# LAN8742A.net
KiCad netlist of a schematic drawn in Altium Designer
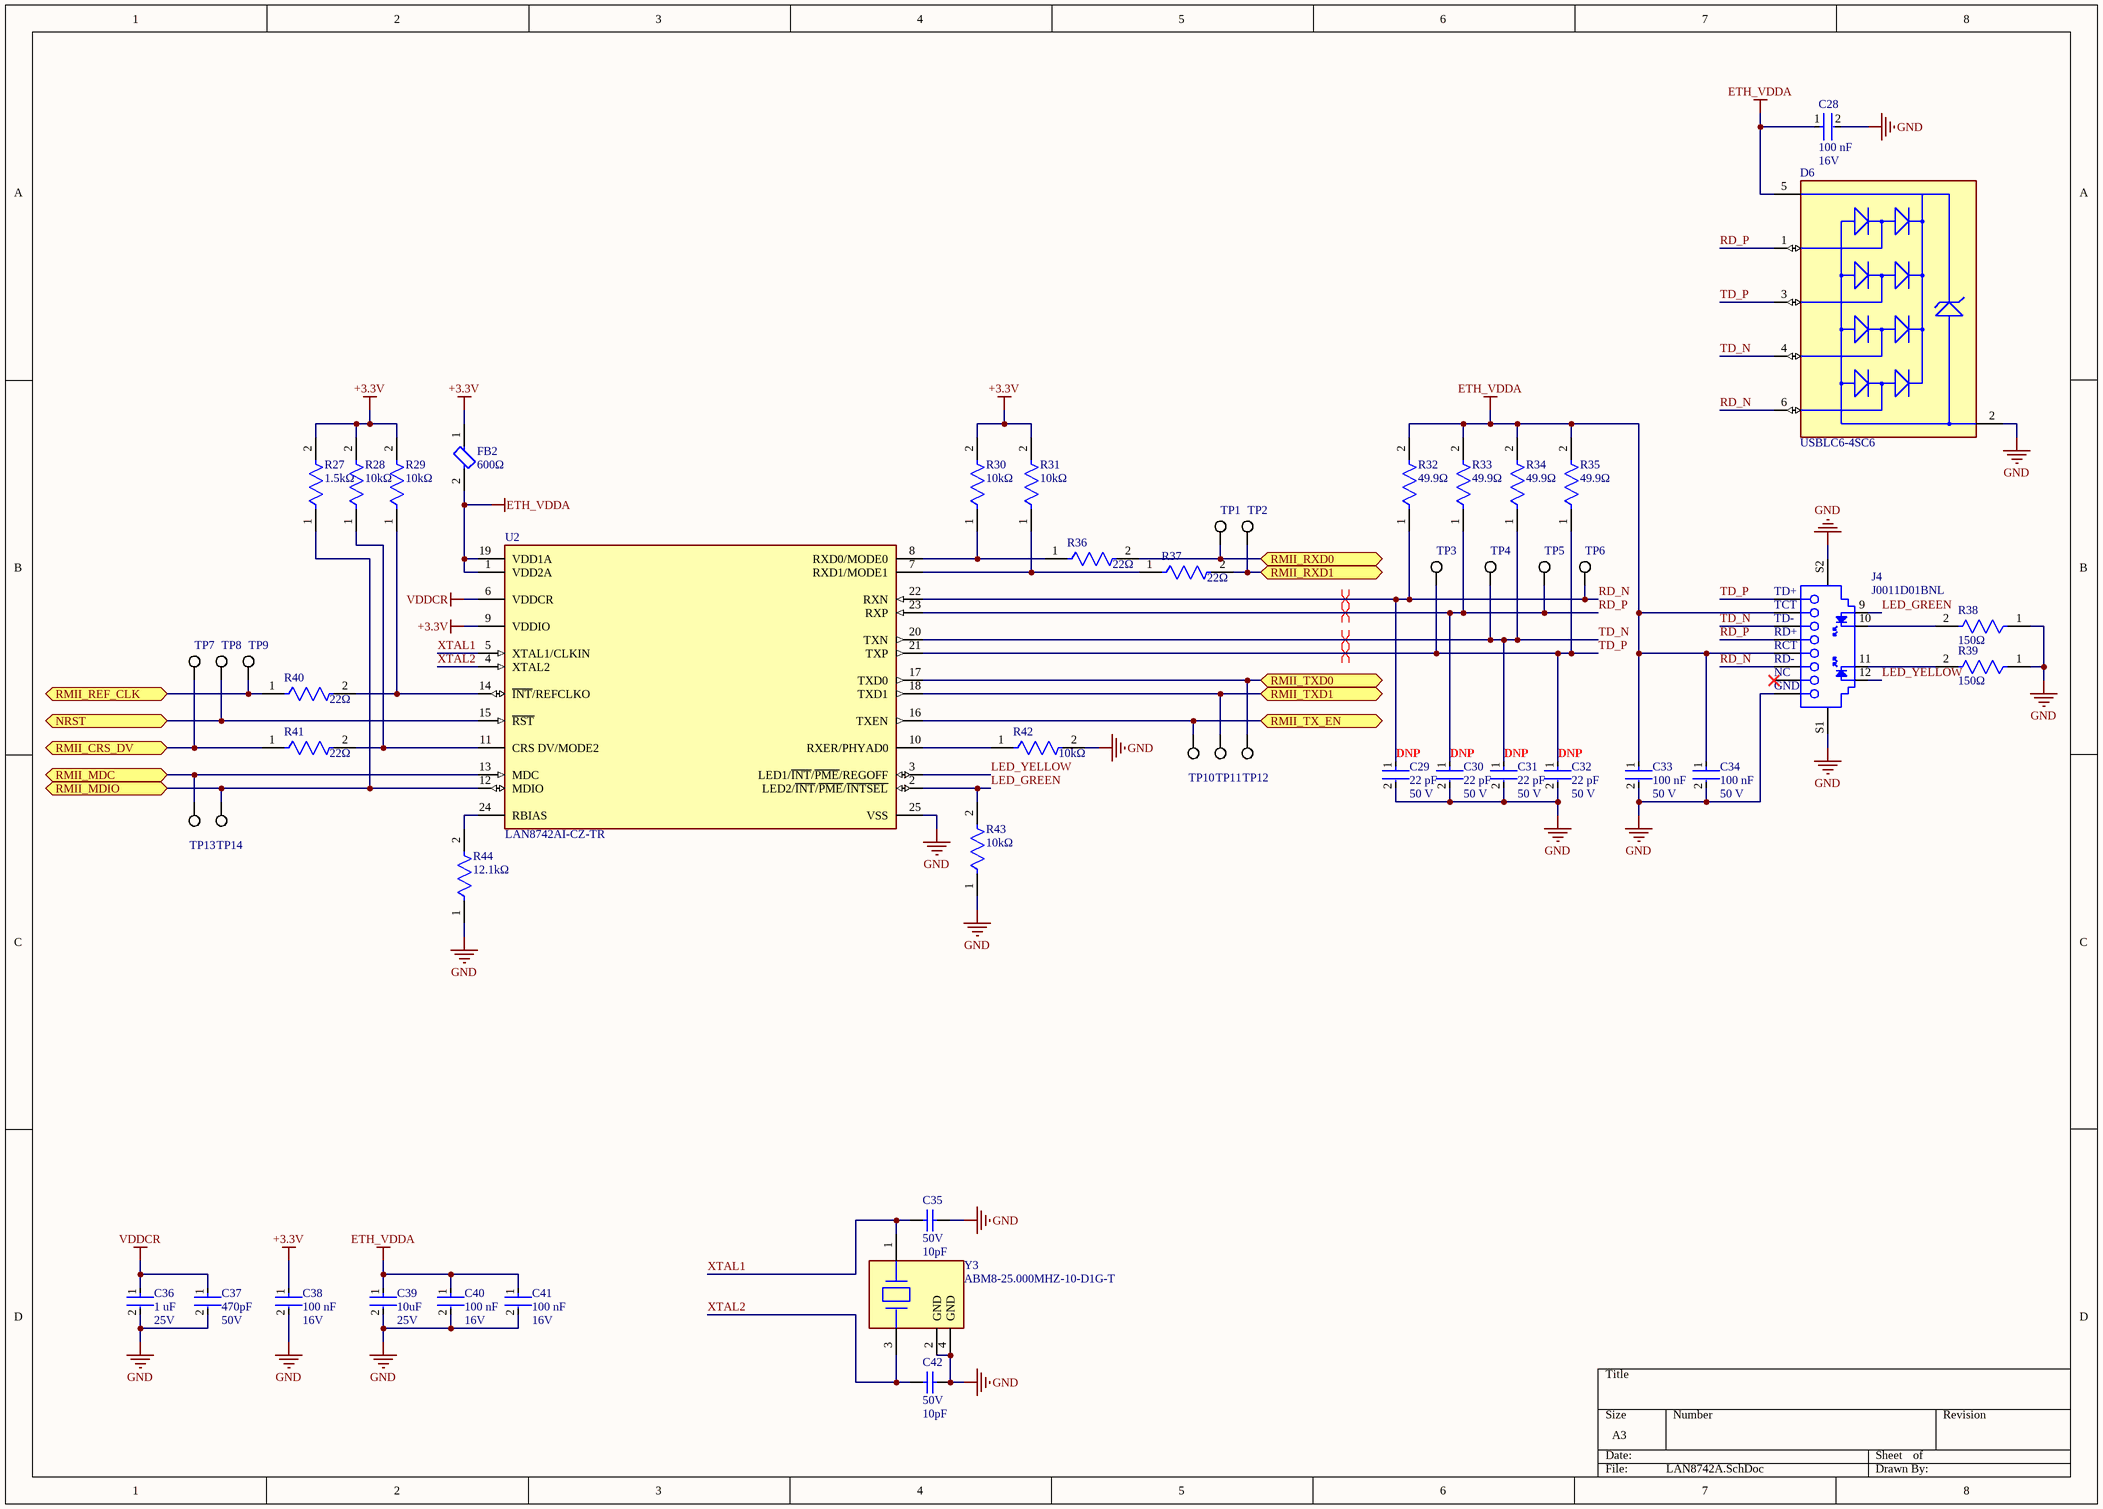
[diagram p0: LAN8742A.SchDoc]

(export (version "E")
  (design (tool "Eeschema 10.0.6"))
  (components
    (comp (ref "C28")
      (value "CL05B104KO5VPNC")
      (footprint "FP-CL752-IPC_B")
      (description "Cap Ceramic 100nF 16V X7R ±10% SMD 0402 +125°C Paper T/R")
      (fields
        (field (name "CAPACITANCE") "100 nF")
        (field (name "VOLTAGE RATING") "16V")
        (field (name "TOLERANCE") "10%")
      )
      (libsource (lib "Altium Content Vault") (part "b4654b650e69147ec39a6b967a45e02"))
    )
    (comp (ref "C29")
      (value "C0402C220K5GACTU")
      (footprint "FP-C0402-BB-IPC_B")
      (description "CAP CER 22PF 50V 10% NP0 0402")
      (fields
        (field (name "OCTOPART") "https://octopart.com/c0402c220k5gactu-kemet-9144192")
        (field (name "CAPACITANCE") "22 pF")
        (field (name "VOLTAGE RATING") "50 V")
        (field (name "TOLERANCE") "0.1")
      )
      (libsource (lib "Altium Content Vault") (part "b4654b650e69147ec39a6b967a45e02"))
    )
    (comp (ref "C30")
      (value "C0402C220K5GACTU")
      (footprint "FP-C0402-BB-IPC_B")
      (description "CAP CER 22PF 50V 10% NP0 0402")
      (fields
        (field (name "OCTOPART") "https://octopart.com/c0402c220k5gactu-kemet-9144192")
        (field (name "CAPACITANCE") "22 pF")
        (field (name "VOLTAGE RATING") "50 V")
        (field (name "TOLERANCE") "0.1")
      )
      (libsource (lib "Altium Content Vault") (part "b4654b650e69147ec39a6b967a45e02"))
    )
    (comp (ref "C31")
      (value "C0402C220K5GACTU")
      (footprint "FP-C0402-BB-IPC_B")
      (description "CAP CER 22PF 50V 10% NP0 0402")
      (fields
        (field (name "OCTOPART") "https://octopart.com/c0402c220k5gactu-kemet-9144192")
        (field (name "CAPACITANCE") "22 pF")
        (field (name "VOLTAGE RATING") "50 V")
        (field (name "TOLERANCE") "0.1")
      )
      (libsource (lib "Altium Content Vault") (part "b4654b650e69147ec39a6b967a45e02"))
    )
    (comp (ref "C32")
      (value "C0402C220K5GACTU")
      (footprint "FP-C0402-BB-IPC_B")
      (description "CAP CER 22PF 50V 10% NP0 0402")
      (fields
        (field (name "OCTOPART") "https://octopart.com/c0402c220k5gactu-kemet-9144192")
        (field (name "CAPACITANCE") "22 pF")
        (field (name "VOLTAGE RATING") "50 V")
        (field (name "TOLERANCE") "0.1")
      )
      (libsource (lib "Altium Content Vault") (part "b4654b650e69147ec39a6b967a45e02"))
    )
    (comp (ref "C33")
      (value "100 nF")
      (footprint "FP-C0603C-CF-IPC_B")
      (description "CAP CER 0.1UF 50V 20% X7R 0603")
      (fields
        (field (name "VOLTAGE RATING") "50 V")
        (field (name "MANUFACTURER PART NUMBER") "C0603C104M5RACTU")
        (field (name "MANUFACTURER") "KEMET")
      )
      (libsource (lib "Altium Content Vault") (part "b4654b650e69147ec39a6b967a45e02"))
    )
    (comp (ref "C34")
      (value "100 nF")
      (footprint "FP-C0603C-CF-IPC_B")
      (description "CAP CER 0.1UF 50V 20% X7R 0603")
      (fields
        (field (name "VOLTAGE RATING") "50 V")
        (field (name "MANUFACTURER PART NUMBER") "C0603C104M5RACTU")
        (field (name "MANUFACTURER") "KEMET")
      )
      (libsource (lib "Altium Content Vault") (part "b4654b650e69147ec39a6b967a45e02"))
    )
    (comp (ref "C35")
      (value "CC0402JRNPO9BN100")
      (footprint "CAPC1005X55X25NL05T05")
      (description "Chip Capacitor, 10 pF, +/- 5%, 50 V, -55 to 125 degC, 0402 (1005 Metric), RoHS, Tape and Reel")
      (fields
        (field (name "TOLERANCE") "5%")
        (field (name "VOLTAGE RATING") "50V")
        (field (name "MANUFACTURER") "Yageo")
        (field (name "CAPACITANCE") "10pF")
      )
      (libsource (lib "Altium Content Vault") (part "CAP-NP-2"))
    )
    (comp (ref "C36")
      (value "GCM188R71E105KA64D")
      (footprint "FP-GCM188-0_1-IPC_B")
      (fields
        (field (name "TOLERANCE") "10%")
        (field (name "CAPACITANCE") "1 uF")
        (field (name "VOLTAGE RATING") "25V")
        (field (name "VOLTAGE") "25V")
      )
      (libsource (lib "Altium Content Vault") (part "02cd4be3c70576c341d710602a673aa"))
    )
    (comp (ref "C37")
      (value "04025C471JAT2A")
      (footprint "FP-0402-L_1_0_1-W_0_5_0_1-MFG")
      (description "General Purpose Ceramic Capacitor, 0402, 470pF, 5%, X7R, 15%, 50V")
      (fields
        (field (name "VOLTAGE") "50V")
        (field (name "TOLERANCE") "5%")
        (field (name "CAPACITANCE") "470pF")
      )
      (libsource (lib "Altium Content Vault") (part "b4654b650e69147ec39a6b967a45e02"))
    )
    (comp (ref "C38")
      (value "CL05B104KO5VPNC")
      (footprint "FP-CL752-IPC_B")
      (description "Cap Ceramic 100nF 16V X7R ±10% SMD 0402 +125°C Paper T/R")
      (fields
        (field (name "CAPACITANCE") "100 nF")
        (field (name "VOLTAGE RATING") "16V")
        (field (name "TOLERANCE") "10%")
      )
      (libsource (lib "Altium Content Vault") (part "b4654b650e69147ec39a6b967a45e02"))
    )
    (comp (ref "C39")
      (value "C1608X5R1E106M080AC")
      (footprint "FP-C1608-080-IPC_B")
      (description "CAP CER 10UF 25V X5R 0603")
      (fields
        (field (name "VOLTAGE RATING") "25V")
        (field (name "TOLERANCE") "20%")
        (field (name "CAPACITANCE") "10uF")
      )
      (libsource (lib "Altium Content Vault") (part "11868f565c42a9108669ba33697ecf6"))
    )
    (comp (ref "C40")
      (value "CL05B104KO5VPNC")
      (footprint "FP-CL752-IPC_B")
      (description "Cap Ceramic 100nF 16V X7R ±10% SMD 0402 +125°C Paper T/R")
      (fields
        (field (name "CAPACITANCE") "100 nF")
        (field (name "VOLTAGE RATING") "16V")
        (field (name "TOLERANCE") "10%")
      )
      (libsource (lib "Altium Content Vault") (part "b4654b650e69147ec39a6b967a45e02"))
    )
    (comp (ref "C41")
      (value "CL05B104KO5VPNC")
      (footprint "FP-CL752-IPC_B")
      (description "Cap Ceramic 100nF 16V X7R ±10% SMD 0402 +125°C Paper T/R")
      (fields
        (field (name "CAPACITANCE") "100 nF")
        (field (name "VOLTAGE RATING") "16V")
        (field (name "TOLERANCE") "10%")
      )
      (libsource (lib "Altium Content Vault") (part "b4654b650e69147ec39a6b967a45e02"))
    )
    (comp (ref "C42")
      (value "CC0402JRNPO9BN100")
      (footprint "CAPC1005X55X25NL05T05")
      (description "Chip Capacitor, 10 pF, +/- 5%, 50 V, -55 to 125 degC, 0402 (1005 Metric), RoHS, Tape and Reel")
      (fields
        (field (name "TOLERANCE") "5%")
        (field (name "VOLTAGE RATING") "50V")
        (field (name "MANUFACTURER") "Yageo")
        (field (name "CAPACITANCE") "10pF")
      )
      (libsource (lib "Altium Content Vault") (part "CAP-NP-2"))
    )
    (comp (ref "D6")
      (value "USBLC6-4SC6")
      (footprint "FP-SOT23-6L-MFG")
      (description "TVS DIODE 5.25V 17V SOT23-6")
      (fields
        (field (name "MANUFACTURER") "STMicroelectronics")
        (field (name "OCTOPART") "https://octopart.com/usblc6-4sc6-stmicroelectronics-347147")
      )
      (libsource (lib "Altium Content Vault") (part "3e70b616ccdc4c88b528e1820c4a7da"))
    )
    (comp (ref "FB2")
      (value "BLM18AG601SN1D")
      (footprint "FP-BLM18-0_15-t0_8-IPC_B")
      (description "Chip Ferrite Bead, 0603, 600Ω @ 100MHz, 0.38Ω, 25%, 500mA")
      (fields (field (name "IMPEDANCE") "600Ω") (field (name "TOLERANCE") "25%"))
      (libsource (lib "Altium Content Vault") (part "5f30dd21d616792df468990f7003faa"))
    )
    (comp (ref "J4")
      (value "J0011D01BNL")
      (footprint "PULS-J0-A_V")
      (fields (field (name "MANUFACTURER") "Pulse Electronics"))
      (libsource (lib "Altium Content Vault") (part "RJ45-12-2SHLD_F"))
    )
    (comp (ref "R27")
      (value "ERJ-2RKF1501X")
      (footprint "FP-ERJ2RK-MFG")
      (description "RES SMD 1.5K OHM 1% 1/10W 0402")
      (fields (field (name "TOLERANCE") "1%") (field (name "RESISTANCE") "1.5kΩ"))
      (libsource (lib "Altium Content Vault") (part "1029c3af85768c4190bb7ad29bc67b5"))
    )
    (comp (ref "R28")
      (value "AC0402FR-0710KL")
      (footprint "FP-AC0402-MFG")
      (description "RES 10kΩ ±1% 0.063W 0402")
      (fields (field (name "TOLERANCE") "1%") (field (name "RESISTANCE") "10kΩ"))
      (libsource (lib "Altium Content Vault") (part "1029c3af85768c4190bb7ad29bc67b5"))
    )
    (comp (ref "R29")
      (value "AC0402FR-0710KL")
      (footprint "FP-AC0402-MFG")
      (description "RES 10kΩ ±1% 0.063W 0402")
      (fields (field (name "TOLERANCE") "1%") (field (name "RESISTANCE") "10kΩ"))
      (libsource (lib "Altium Content Vault") (part "1029c3af85768c4190bb7ad29bc67b5"))
    )
    (comp (ref "R30")
      (value "AC0402FR-0710KL")
      (footprint "FP-AC0402-MFG")
      (description "RES 10kΩ ±1% 0.063W 0402")
      (fields (field (name "TOLERANCE") "1%") (field (name "RESISTANCE") "10kΩ"))
      (libsource (lib "Altium Content Vault") (part "1029c3af85768c4190bb7ad29bc67b5"))
    )
    (comp (ref "R31")
      (value "AC0402FR-0710KL")
      (footprint "FP-AC0402-MFG")
      (description "RES 10kΩ ±1% 0.063W 0402")
      (fields (field (name "TOLERANCE") "1%") (field (name "RESISTANCE") "10kΩ"))
      (libsource (lib "Altium Content Vault") (part "1029c3af85768c4190bb7ad29bc67b5"))
    )
    (comp (ref "R32")
      (value "AC0402FR-0749R9L")
      (footprint "FP-AC0402-MFG")
      (description "RES 49.9Ω ±1% 0.063W 0402")
      (fields (field (name "TOLERANCE") "1%") (field (name "RESISTANCE") "49.9Ω"))
      (libsource (lib "Altium Content Vault") (part "1029c3af85768c4190bb7ad29bc67b5"))
    )
    (comp (ref "R33")
      (value "AC0402FR-0749R9L")
      (footprint "FP-AC0402-MFG")
      (description "RES 49.9Ω ±1% 0.063W 0402")
      (fields (field (name "TOLERANCE") "1%") (field (name "RESISTANCE") "49.9Ω"))
      (libsource (lib "Altium Content Vault") (part "1029c3af85768c4190bb7ad29bc67b5"))
    )
    (comp (ref "R34")
      (value "AC0402FR-0749R9L")
      (footprint "FP-AC0402-MFG")
      (description "RES 49.9Ω ±1% 0.063W 0402")
      (fields (field (name "TOLERANCE") "1%") (field (name "RESISTANCE") "49.9Ω"))
      (libsource (lib "Altium Content Vault") (part "1029c3af85768c4190bb7ad29bc67b5"))
    )
    (comp (ref "R35")
      (value "AC0402FR-0749R9L")
      (footprint "FP-AC0402-MFG")
      (description "RES 49.9Ω ±1% 0.063W 0402")
      (fields (field (name "TOLERANCE") "1%") (field (name "RESISTANCE") "49.9Ω"))
      (libsource (lib "Altium Content Vault") (part "1029c3af85768c4190bb7ad29bc67b5"))
    )
    (comp (ref "R36")
      (value "AC0402FR-0722RL")
      (footprint "FP-AC0402-MFG")
      (description "RES 22Ω ±1% 0.063W 0402")
      (fields (field (name "TOLERANCE") "1%") (field (name "RESISTANCE") "22Ω"))
      (libsource (lib "Altium Content Vault") (part "1029c3af85768c4190bb7ad29bc67b5"))
    )
    (comp (ref "R37")
      (value "AC0402FR-0722RL")
      (footprint "FP-AC0402-MFG")
      (description "RES 22Ω ±1% 0.063W 0402")
      (fields (field (name "TOLERANCE") "1%") (field (name "RESISTANCE") "22Ω"))
      (libsource (lib "Altium Content Vault") (part "1029c3af85768c4190bb7ad29bc67b5"))
    )
    (comp (ref "R38")
      (value "CRCW0603150RFKEA")
      (footprint "FP-CRCW0603-e3-IPC_B")
      (description "RES Thick Film, 150Ω, 1%, 0.1W, 100ppm/°C, 0603")
      (fields (field (name "TOLERANCE") "1%") (field (name "RESISTANCE") "150Ω"))
      (libsource (lib "Altium Content Vault") (part "1029c3af85768c4190bb7ad29bc67b5"))
    )
    (comp (ref "R39")
      (value "CRCW0603150RFKEA")
      (footprint "FP-CRCW0603-e3-IPC_B")
      (description "RES Thick Film, 150Ω, 1%, 0.1W, 100ppm/°C, 0603")
      (fields (field (name "TOLERANCE") "1%") (field (name "RESISTANCE") "150Ω"))
      (libsource (lib "Altium Content Vault") (part "1029c3af85768c4190bb7ad29bc67b5"))
    )
    (comp (ref "R40")
      (value "AC0402FR-0722RL")
      (footprint "FP-AC0402-MFG")
      (description "RES 22Ω ±1% 0.063W 0402")
      (fields (field (name "TOLERANCE") "1%") (field (name "RESISTANCE") "22Ω"))
      (libsource (lib "Altium Content Vault") (part "1029c3af85768c4190bb7ad29bc67b5"))
    )
    (comp (ref "R41")
      (value "AC0402FR-0722RL")
      (footprint "FP-AC0402-MFG")
      (description "RES 22Ω ±1% 0.063W 0402")
      (fields (field (name "TOLERANCE") "1%") (field (name "RESISTANCE") "22Ω"))
      (libsource (lib "Altium Content Vault") (part "1029c3af85768c4190bb7ad29bc67b5"))
    )
    (comp (ref "R42")
      (value "AC0402FR-0710KL")
      (footprint "FP-AC0402-MFG")
      (description "RES 10kΩ ±1% 0.063W 0402")
      (fields (field (name "TOLERANCE") "1%") (field (name "RESISTANCE") "10kΩ"))
      (libsource (lib "Altium Content Vault") (part "1029c3af85768c4190bb7ad29bc67b5"))
    )
    (comp (ref "R43")
      (value "RC0603FR-0710KL")
      (footprint "FP-RC0603-0_55-IPC_B")
      (description "RES 10K OHM 1% 1/10W 0603")
      (fields (field (name "TOLERANCE") "1%") (field (name "RESISTANCE") "10kΩ"))
      (libsource (lib "Altium Content Vault") (part "1029c3af85768c4190bb7ad29bc67b5"))
    )
    (comp (ref "R44")
      (value "ERJ-2RKF1212X")
      (footprint "FP-ERJ2RK-MFG")
      (description "RES SMD 12.1K OHM 1% 1/10W 0402")
      (fields (field (name "RESISTANCE") "12.1kΩ") (field (name "TOLERANCE") "1%"))
      (libsource (lib "Altium Content Vault") (part "1029c3af85768c4190bb7ad29bc67b5"))
    )
    (comp (ref "TP1")
      (value "5019")
      (footprint "KSTN-5019_V")
      (description "Test Point, 1 Position SMD, RoHS, Tape and Reel")
      (libsource (lib "Altium Content Vault") (part "TESTPOINT_WHITE"))
    )
    (comp (ref "TP2")
      (value "5019")
      (footprint "KSTN-5019_V")
      (description "Test Point, 1 Position SMD, RoHS, Tape and Reel")
      (libsource (lib "Altium Content Vault") (part "TESTPOINT_WHITE"))
    )
    (comp (ref "TP3")
      (value "5019")
      (footprint "KSTN-5019_V")
      (description "Test Point, 1 Position SMD, RoHS, Tape and Reel")
      (libsource (lib "Altium Content Vault") (part "TESTPOINT_WHITE"))
    )
    (comp (ref "TP4")
      (value "5019")
      (footprint "KSTN-5019_V")
      (description "Test Point, 1 Position SMD, RoHS, Tape and Reel")
      (libsource (lib "Altium Content Vault") (part "TESTPOINT_WHITE"))
    )
    (comp (ref "TP5")
      (value "5019")
      (footprint "KSTN-5019_V")
      (description "Test Point, 1 Position SMD, RoHS, Tape and Reel")
      (libsource (lib "Altium Content Vault") (part "TESTPOINT_WHITE"))
    )
    (comp (ref "TP6")
      (value "5019")
      (footprint "KSTN-5019_V")
      (description "Test Point, 1 Position SMD, RoHS, Tape and Reel")
      (libsource (lib "Altium Content Vault") (part "TESTPOINT_WHITE"))
    )
    (comp (ref "TP7")
      (value "5019")
      (footprint "KSTN-5019_V")
      (description "Test Point, 1 Position SMD, RoHS, Tape and Reel")
      (libsource (lib "Altium Content Vault") (part "TESTPOINT_WHITE"))
    )
    (comp (ref "TP8")
      (value "5019")
      (footprint "KSTN-5019_V")
      (description "Test Point, 1 Position SMD, RoHS, Tape and Reel")
      (libsource (lib "Altium Content Vault") (part "TESTPOINT_WHITE"))
    )
    (comp (ref "TP9")
      (value "5019")
      (footprint "KSTN-5019_V")
      (description "Test Point, 1 Position SMD, RoHS, Tape and Reel")
      (libsource (lib "Altium Content Vault") (part "TESTPOINT_WHITE"))
    )
    (comp (ref "TP10")
      (value "5019")
      (footprint "KSTN-5019_V")
      (description "Test Point, 1 Position SMD, RoHS, Tape and Reel")
      (libsource (lib "Altium Content Vault") (part "TESTPOINT_WHITE"))
    )
    (comp (ref "TP11")
      (value "5019")
      (footprint "KSTN-5019_V")
      (description "Test Point, 1 Position SMD, RoHS, Tape and Reel")
      (libsource (lib "Altium Content Vault") (part "TESTPOINT_WHITE"))
    )
    (comp (ref "TP12")
      (value "5019")
      (footprint "KSTN-5019_V")
      (description "Test Point, 1 Position SMD, RoHS, Tape and Reel")
      (libsource (lib "Altium Content Vault") (part "TESTPOINT_WHITE"))
    )
    (comp (ref "TP13")
      (value "5019")
      (footprint "KSTN-5019_V")
      (description "Test Point, 1 Position SMD, RoHS, Tape and Reel")
      (libsource (lib "Altium Content Vault") (part "TESTPOINT_WHITE"))
    )
    (comp (ref "TP14")
      (value "5019")
      (footprint "KSTN-5019_V")
      (description "Test Point, 1 Position SMD, RoHS, Tape and Reel")
      (libsource (lib "Altium Content Vault") (part "TESTPOINT_WHITE"))
    )
    (comp (ref "U2")
      (value "LAN8742AI-CZ-TR")
      (footprint "FP-C04-143-MFG")
      (description "IC TRANSCEIVER FULL 1/1 24SQFN")
      (fields
        (field (name "MANUFACTURER") "Microchip")
        (field (name "OCTOPART") "https://octopart.com/lan8742ai-cz-tr-microchip-29030589")
      )
      (libsource (lib "Altium Content Vault") (part "663acb86b5908f69048389f16eb1286"))
    )
    (comp (ref "Y3")
      (value "ABM8-25.000MHZ-10-D1G-T")
      (footprint "FP-ABM8-MFG")
      (description "Crystal 25MHz ±10ppm 10pF SMD-4 3.2mm x 2.5mm")
      (libsource (lib "Altium Content Vault") (part "dfdb7f9a12507849fb681da9a70121c"))
    )
  )
  (nets
    (net (code "1") (name "+3.3V") (class "Default")
      (node (ref "C38") (pin "1") (pinfunction "1_1") (pintype "passive"))
      (node (ref "FB2") (pin "1") (pinfunction "1_1") (pintype "passive"))
      (node (ref "R27") (pin "2") (pinfunction "2_2") (pintype "passive"))
      (node (ref "R28") (pin "2") (pinfunction "2_2") (pintype "passive"))
      (node (ref "R29") (pin "2") (pinfunction "2_2") (pintype "passive"))
      (node (ref "R30") (pin "2") (pinfunction "2_2") (pintype "passive"))
      (node (ref "R31") (pin "2") (pinfunction "2_2") (pintype "passive"))
      (node (ref "U2") (pin "9") (pinfunction "VDDIO_9") (pintype "power_in"))
    )
    (net (code "2") (name "/LED_GREEN") (class "Default")
      (node (ref "J4") (pin "9") (pinfunction "9_9") (pintype "passive"))
      (node (ref "R43") (pin "2") (pinfunction "2_2") (pintype "passive"))
      (node (ref "U2") (pin "2") (pinfunction "LED2/~{INT}/~{PME}/~{INTSEL}_2") (pintype "bidirectional"))
    )
    (net (code "3") (name "/LED_YELLOW") (class "Default")
      (node (ref "J4") (pin "12") (pinfunction "12_12") (pintype "passive"))
      (node (ref "U2") (pin "3") (pinfunction "LED1/~{INT}/~{PME}/REGOFF_3") (pintype "bidirectional"))
    )
    (net (code "4") (name "/NRST") (class "Default")
      (node (ref "TP8") (pin "1") (pinfunction "1_1") (pintype "passive"))
      (node (ref "U2") (pin "15") (pinfunction "~{RST}_15") (pintype "input"))
    )
    (net (code "5") (name "/RD_N") (class "Default")
      (node (ref "C29") (pin "1") (pinfunction "1_1") (pintype "passive"))
      (node (ref "D6") (pin "6") (pinfunction "I/O4_6") (pintype "bidirectional"))
      (node (ref "J4") (pin "6") (pinfunction "RD-_6") (pintype "passive"))
      (node (ref "R32") (pin "1") (pinfunction "1_1") (pintype "passive"))
      (node (ref "TP6") (pin "1") (pinfunction "1_1") (pintype "passive"))
      (node (ref "U2") (pin "22") (pinfunction "RXN_22") (pintype "input"))
    )
    (net (code "6") (name "/RD_P") (class "Default")
      (node (ref "C30") (pin "1") (pinfunction "1_1") (pintype "passive"))
      (node (ref "D6") (pin "1") (pinfunction "I/O1_1") (pintype "bidirectional"))
      (node (ref "J4") (pin "4") (pinfunction "RD+_4") (pintype "passive"))
      (node (ref "R33") (pin "1") (pinfunction "1_1") (pintype "passive"))
      (node (ref "TP5") (pin "1") (pinfunction "1_1") (pintype "passive"))
      (node (ref "U2") (pin "23") (pinfunction "RXP_23") (pintype "input"))
    )
    (net (code "7") (name "/RMII_CRS_DV") (class "Default")
      (node (ref "R41") (pin "1") (pinfunction "1_1") (pintype "passive"))
      (node (ref "TP7") (pin "1") (pinfunction "1_1") (pintype "passive"))
    )
    (net (code "8") (name "/RMII_MDC") (class "Default")
      (node (ref "TP13") (pin "1") (pinfunction "1_1") (pintype "passive"))
      (node (ref "U2") (pin "13") (pinfunction "MDC_13") (pintype "input"))
    )
    (net (code "9") (name "/RMII_MDIO") (class "Default")
      (node (ref "R27") (pin "1") (pinfunction "1_1") (pintype "passive"))
      (node (ref "TP14") (pin "1") (pinfunction "1_1") (pintype "passive"))
      (node (ref "U2") (pin "12") (pinfunction "MDIO_12") (pintype "bidirectional"))
    )
    (net (code "10") (name "/RMII_REF_CLK") (class "Default")
      (node (ref "R40") (pin "1") (pinfunction "1_1") (pintype "passive"))
      (node (ref "TP9") (pin "1") (pinfunction "1_1") (pintype "passive"))
    )
    (net (code "11") (name "/RMII_RXD0") (class "Default")
      (node (ref "R36") (pin "2") (pinfunction "2_2") (pintype "passive"))
      (node (ref "TP1") (pin "1") (pinfunction "1_1") (pintype "passive"))
    )
    (net (code "12") (name "/RMII_RXD1") (class "Default")
      (node (ref "R37") (pin "2") (pinfunction "2_2") (pintype "passive"))
      (node (ref "TP2") (pin "1") (pinfunction "1_1") (pintype "passive"))
    )
    (net (code "13") (name "/RMII_TXD0") (class "Default")
      (node (ref "TP12") (pin "1") (pinfunction "1_1") (pintype "passive"))
      (node (ref "U2") (pin "17") (pinfunction "TXD0_17") (pintype "output"))
    )
    (net (code "14") (name "/RMII_TXD1") (class "Default")
      (node (ref "TP11") (pin "1") (pinfunction "1_1") (pintype "passive"))
      (node (ref "U2") (pin "18") (pinfunction "TXD1_18") (pintype "output"))
    )
    (net (code "15") (name "/RMII_TX_EN") (class "Default")
      (node (ref "TP10") (pin "1") (pinfunction "1_1") (pintype "passive"))
      (node (ref "U2") (pin "16") (pinfunction "TXEN_16") (pintype "output"))
    )
    (net (code "16") (name "/TD_N") (class "Default")
      (node (ref "C31") (pin "1") (pinfunction "1_1") (pintype "passive"))
      (node (ref "D6") (pin "4") (pinfunction "I/O3_4") (pintype "bidirectional"))
      (node (ref "J4") (pin "3") (pinfunction "TD-_3") (pintype "passive"))
      (node (ref "R34") (pin "1") (pinfunction "1_1") (pintype "passive"))
      (node (ref "TP4") (pin "1") (pinfunction "1_1") (pintype "passive"))
      (node (ref "U2") (pin "20") (pinfunction "TXN_20") (pintype "output"))
    )
    (net (code "17") (name "/TD_P") (class "Default")
      (node (ref "C32") (pin "1") (pinfunction "1_1") (pintype "passive"))
      (node (ref "D6") (pin "3") (pinfunction "I/O2_3") (pintype "bidirectional"))
      (node (ref "J4") (pin "1") (pinfunction "TD+_1") (pintype "passive"))
      (node (ref "R35") (pin "1") (pinfunction "1_1") (pintype "passive"))
      (node (ref "TP3") (pin "1") (pinfunction "1_1") (pintype "passive"))
      (node (ref "U2") (pin "21") (pinfunction "TXP_21") (pintype "output"))
    )
    (net (code "18") (name "/XTAL1") (class "Default")
      (node (ref "C35") (pin "1") (pinfunction "1_1") (pintype "passive"))
      (node (ref "U2") (pin "5") (pinfunction "XTAL1/CLKIN_5") (pintype "input"))
      (node (ref "Y3") (pin "1") (pinfunction "1_1") (pintype "passive"))
    )
    (net (code "19") (name "/XTAL2") (class "Default")
      (node (ref "C42") (pin "1") (pinfunction "1_1") (pintype "passive"))
      (node (ref "U2") (pin "4") (pinfunction "XTAL2_4") (pintype "input"))
      (node (ref "Y3") (pin "3") (pinfunction "3_3") (pintype "passive"))
    )
    (net (code "20") (name "ETH_VDDA") (class "Default")
      (node (ref "C28") (pin "1") (pinfunction "1_1") (pintype "passive"))
      (node (ref "C33") (pin "1") (pinfunction "1_1") (pintype "passive"))
      (node (ref "C34") (pin "1") (pinfunction "1_1") (pintype "passive"))
      (node (ref "C39") (pin "1") (pinfunction "1_1") (pintype "passive"))
      (node (ref "C40") (pin "1") (pinfunction "1_1") (pintype "passive"))
      (node (ref "C41") (pin "1") (pinfunction "1_1") (pintype "passive"))
      (node (ref "D6") (pin "5") (pinfunction "VBUS_5") (pintype "power_in"))
      (node (ref "FB2") (pin "2") (pinfunction "2_2") (pintype "passive"))
      (node (ref "J4") (pin "2") (pinfunction "TCT_2") (pintype "passive"))
      (node (ref "J4") (pin "5") (pinfunction "RCT_5") (pintype "passive"))
      (node (ref "R32") (pin "2") (pinfunction "2_2") (pintype "passive"))
      (node (ref "R33") (pin "2") (pinfunction "2_2") (pintype "passive"))
      (node (ref "R34") (pin "2") (pinfunction "2_2") (pintype "passive"))
      (node (ref "R35") (pin "2") (pinfunction "2_2") (pintype "passive"))
      (node (ref "U2") (pin "1") (pinfunction "VDD2A_1") (pintype "power_in"))
      (node (ref "U2") (pin "19") (pinfunction "VDD1A_19") (pintype "power_in"))
    )
    (net (code "21") (name "GND") (class "Default")
      (node (ref "C28") (pin "2") (pinfunction "2_2") (pintype "passive"))
      (node (ref "C29") (pin "2") (pinfunction "2_2") (pintype "passive"))
      (node (ref "C30") (pin "2") (pinfunction "2_2") (pintype "passive"))
      (node (ref "C31") (pin "2") (pinfunction "2_2") (pintype "passive"))
      (node (ref "C32") (pin "2") (pinfunction "2_2") (pintype "passive"))
      (node (ref "C33") (pin "2") (pinfunction "2_2") (pintype "passive"))
      (node (ref "C34") (pin "2") (pinfunction "2_2") (pintype "passive"))
      (node (ref "C35") (pin "2") (pinfunction "2_2") (pintype "passive"))
      (node (ref "C36") (pin "2") (pinfunction "2_2") (pintype "passive"))
      (node (ref "C37") (pin "2") (pinfunction "2_2") (pintype "passive"))
      (node (ref "C38") (pin "2") (pinfunction "2_2") (pintype "passive"))
      (node (ref "C39") (pin "2") (pinfunction "2_2") (pintype "passive"))
      (node (ref "C40") (pin "2") (pinfunction "2_2") (pintype "passive"))
      (node (ref "C41") (pin "2") (pinfunction "2_2") (pintype "passive"))
      (node (ref "C42") (pin "2") (pinfunction "2_2") (pintype "passive"))
      (node (ref "D6") (pin "2") (pinfunction "GND_2") (pintype "power_in"))
      (node (ref "J4") (pin "8") (pinfunction "GND_8") (pintype "passive"))
      (node (ref "J4") (pin "S1") (pinfunction "S1_S1") (pintype "passive"))
      (node (ref "J4") (pin "S2") (pinfunction "S2_S2") (pintype "passive"))
      (node (ref "R38") (pin "1") (pinfunction "1_1") (pintype "passive"))
      (node (ref "R39") (pin "1") (pinfunction "1_1") (pintype "passive"))
      (node (ref "R42") (pin "2") (pinfunction "2_2") (pintype "passive"))
      (node (ref "R43") (pin "1") (pinfunction "1_1") (pintype "passive"))
      (node (ref "R44") (pin "1") (pinfunction "1_1") (pintype "passive"))
      (node (ref "U2") (pin "25") (pinfunction "VSS_25") (pintype "power_in"))
      (node (ref "Y3") (pin "2") (pinfunction "GND_2") (pintype "power_in"))
      (node (ref "Y3") (pin "4") (pinfunction "GND_4") (pintype "power_in"))
    )
    (net (code "22") (name "Net-(J4-Pad10)") (class "Default")
      (node (ref "J4") (pin "10") (pinfunction "10_10") (pintype "passive"))
      (node (ref "R38") (pin "2") (pinfunction "2_2") (pintype "passive"))
    )
    (net (code "23") (name "Net-(J4-Pad11)") (class "Default")
      (node (ref "J4") (pin "11") (pinfunction "11_11") (pintype "passive"))
      (node (ref "R39") (pin "2") (pinfunction "2_2") (pintype "passive"))
    )
    (net (code "24") (name "Net-(U2-CRS_DV{slash}MODE2)") (class "Default")
      (node (ref "R28") (pin "1") (pinfunction "1_1") (pintype "passive"))
      (node (ref "R41") (pin "2") (pinfunction "2_2") (pintype "passive"))
      (node (ref "U2") (pin "11") (pinfunction "CRS_DV/MODE2_11") (pintype "passive"))
    )
    (net (code "25") (name "Net-(U2-RBIAS)") (class "Default")
      (node (ref "R44") (pin "2") (pinfunction "2_2") (pintype "passive"))
      (node (ref "U2") (pin "24") (pinfunction "RBIAS_24") (pintype "passive"))
    )
    (net (code "26") (name "Net-(U2-RXD0{slash}MODE0)") (class "Default")
      (node (ref "R30") (pin "1") (pinfunction "1_1") (pintype "passive"))
      (node (ref "R36") (pin "1") (pinfunction "1_1") (pintype "passive"))
      (node (ref "U2") (pin "8") (pinfunction "RXD0/MODE0_8") (pintype "passive"))
    )
    (net (code "27") (name "Net-(U2-RXD1{slash}MODE1)") (class "Default")
      (node (ref "R31") (pin "1") (pinfunction "1_1") (pintype "passive"))
      (node (ref "R37") (pin "1") (pinfunction "1_1") (pintype "passive"))
      (node (ref "U2") (pin "7") (pinfunction "RXD1/MODE1_7") (pintype "passive"))
    )
    (net (code "28") (name "Net-(U2-RXER{slash}PHYAD0)") (class "Default")
      (node (ref "R42") (pin "1") (pinfunction "1_1") (pintype "passive"))
      (node (ref "U2") (pin "10") (pinfunction "RXER/PHYAD0_10") (pintype "passive"))
    )
    (net (code "29") (name "Net-(U2-~{INT}{slash}REFCLKO)") (class "Default")
      (node (ref "R29") (pin "1") (pinfunction "1_1") (pintype "passive"))
      (node (ref "R40") (pin "2") (pinfunction "2_2") (pintype "passive"))
      (node (ref "U2") (pin "14") (pinfunction "~{INT}/REFCLKO_14") (pintype "bidirectional"))
    )
    (net (code "30") (name "VDDCR") (class "Default")
      (node (ref "C36") (pin "1") (pinfunction "1_1") (pintype "passive"))
      (node (ref "C37") (pin "1") (pinfunction "1_1") (pintype "passive"))
      (node (ref "U2") (pin "6") (pinfunction "VDDCR_6") (pintype "power_in"))
    )
    (net (code "31") (name "unconnected-(J4-NC-Pad7)") (class "Default")
      (node (ref "J4") (pin "7") (pinfunction "NC_7") (pintype "passive+no_connect"))
    )
  )
)
